# Analog_sensor_revA.net
KiCad netlist of a schematic drawn in EAGLE
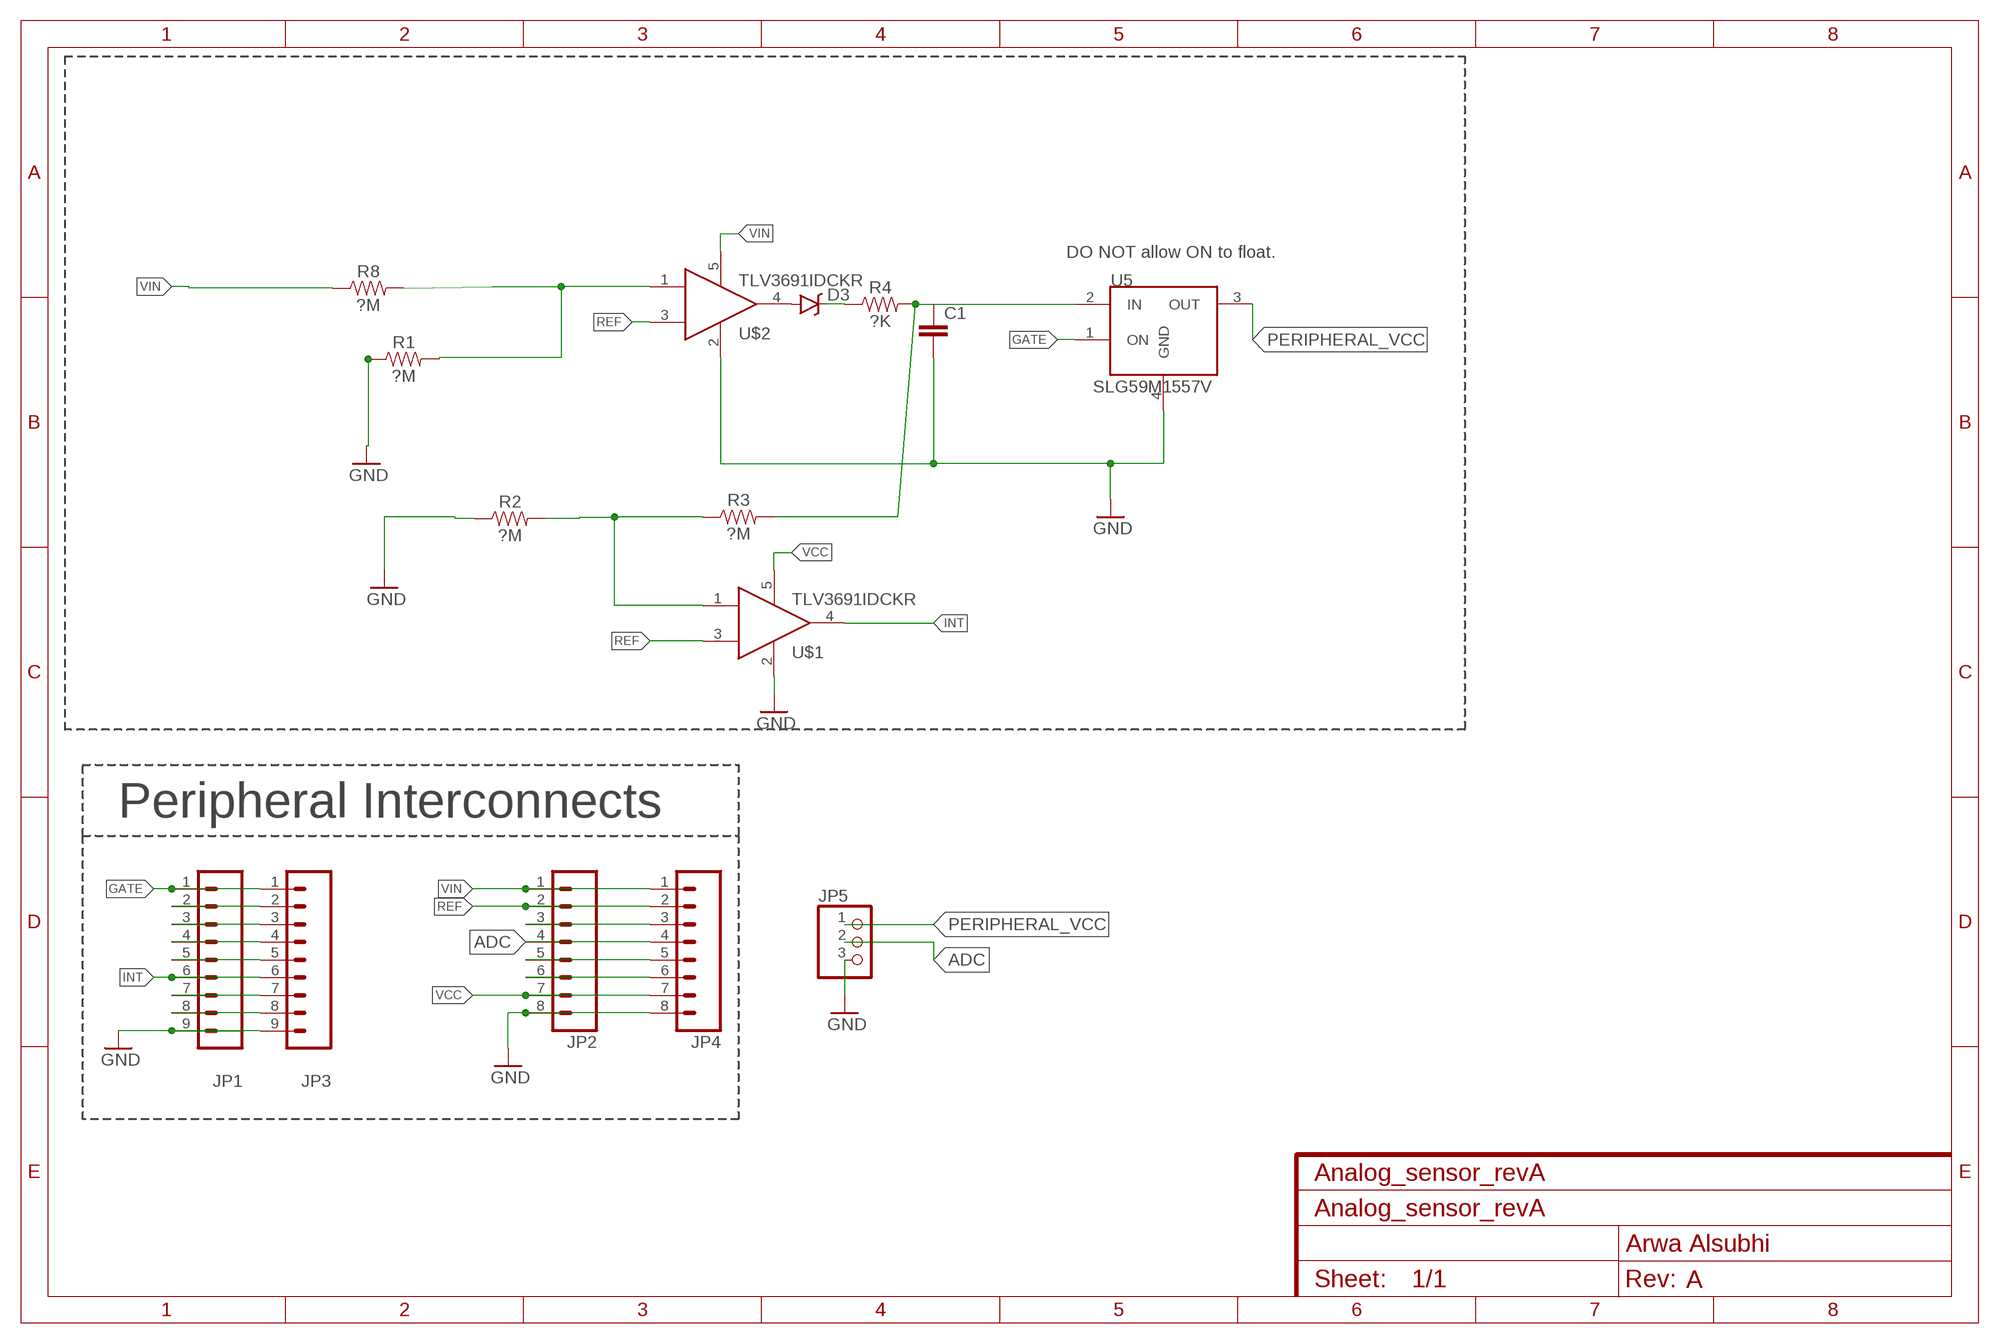
[diagram p0: schematic, sheet 1]

(export (version "E")
  (design (tool "Eeschema 10.0.6"))
  (components
    (comp (ref "C1")
      (value "CAP0603-CAP")
      (footprint "eagle-import:0603-CAP")
      (libsource (lib "eagle-import") (part "CAP0603-CAP"))
    )
    (comp (ref "D3")
      (value "RB751")
      (footprint "eagle-import:SOD-523")
      (fields (field (name "MPN") "BAS40-02V-V-G-08"))
      (libsource (lib "eagle-import") (part "DIODE-SCHOTTKY-RB751"))
    )
    (comp (ref "JP1")
      (value "M091.27MM")
      (footprint "eagle-import:1X09-1.27MM")
      (fields (field (name "MANUFACTURERPARTNUMBER") "GRPB091VWVN-RC ") (field (name "MPN") "GRPB091VWVN-RC"))
      (libsource (lib "eagle-import") (part "M091.27MM"))
    )
    (comp (ref "JP2")
      (value "M081.27MM")
      (footprint "eagle-import:1X08-1.27MM")
      (fields (field (name "MANUFACTURERPARTNUMBER") "GRPB081VWVN-RC "))
      (libsource (lib "eagle-import") (part "M081.27MM"))
    )
    (comp (ref "JP3")
      (value "M091.27MM")
      (footprint "eagle-import:1X09-1.27MM")
      (fields (field (name "MANUFACTURERPARTNUMBER") "GRPB091VWVN-RC ") (field (name "MPN") "GRPB091VWVN-RC"))
      (libsource (lib "eagle-import") (part "M091.27MM"))
    )
    (comp (ref "JP4")
      (value "M081.27MM")
      (footprint "eagle-import:1X08-1.27MM")
      (fields (field (name "MANUFACTURERPARTNUMBER") "GRPB081VWVN-RC "))
      (libsource (lib "eagle-import") (part "M081.27MM"))
    )
    (comp (ref "JP5")
      (value "PINHD-1X3")
      (footprint "eagle-import:1X03")
      (libsource (lib "eagle-import") (part "PINHD-1X3"))
    )
    (comp (ref "R1")
      (value "?M")
      (footprint "eagle-import:0805")
      (libsource (lib "eagle-import") (part "0.3OHM-0805-1/8W-1%"))
    )
    (comp (ref "R2")
      (value "?M")
      (footprint "eagle-import:0805")
      (libsource (lib "eagle-import") (part "0.3OHM-0805-1/8W-1%"))
    )
    (comp (ref "R3")
      (value "?M")
      (footprint "eagle-import:0805")
      (libsource (lib "eagle-import") (part "0.3OHM-0805-1/8W-1%"))
    )
    (comp (ref "R4")
      (value "?K")
      (footprint "eagle-import:0805")
      (libsource (lib "eagle-import") (part "0.3OHM-0805-1/8W-1%"))
    )
    (comp (ref "R8")
      (value "?M")
      (footprint "eagle-import:0805")
      (libsource (lib "eagle-import") (part "0.3OHM-0805-1/8W-1%"))
    )
    (comp (ref "U$1")
      (value "TLV3691IDCKR")
      (footprint "eagle-import:SOT353")
      (libsource (lib "eagle-import") (part "TLV3691IDCKR"))
    )
    (comp (ref "U$2")
      (value "TLV3691IDCKR")
      (footprint "eagle-import:SOT353")
      (libsource (lib "eagle-import") (part "TLV3691IDCKR"))
    )
    (comp (ref "U5")
      (value "SLG59M1557V")
      (footprint "eagle-import:4STDFN")
      (fields (field (name "MPN") "SLG59M1557V "))
      (libsource (lib "eagle-import") (part "SLG59M1557V"))
    )
  )
  (nets
    (net (code "1") (name "ADC") (class "Default")
      (node (ref "JP2") (pin "4") (pinfunction "4_4") (pintype "passive"))
      (node (ref "JP4") (pin "4") (pinfunction "4_4") (pintype "passive"))
      (node (ref "JP5") (pin "2") (pinfunction "2_2") (pintype "passive"))
    )
    (net (code "2") (name "GATE") (class "Default")
      (node (ref "JP1") (pin "1") (pinfunction "1_1") (pintype "passive"))
      (node (ref "JP3") (pin "1") (pinfunction "1_1") (pintype "passive"))
      (node (ref "U5") (pin "1") (pinfunction "ON_1") (pintype "bidirectional"))
    )
    (net (code "3") (name "GND") (class "Default")
      (node (ref "C1") (pin "2") (pinfunction "2_2") (pintype "passive"))
      (node (ref "JP1") (pin "9") (pinfunction "9_9") (pintype "passive"))
      (node (ref "JP2") (pin "8") (pinfunction "8_8") (pintype "passive"))
      (node (ref "JP3") (pin "9") (pinfunction "9_9") (pintype "passive"))
      (node (ref "JP4") (pin "8") (pinfunction "8_8") (pintype "passive"))
      (node (ref "JP5") (pin "3") (pinfunction "3_3") (pintype "passive"))
      (node (ref "R1") (pin "1") (pinfunction "1_1") (pintype "passive"))
      (node (ref "R2") (pin "1") (pinfunction "1_1") (pintype "passive"))
      (node (ref "U$1") (pin "2") (pinfunction "2_2") (pintype "bidirectional"))
      (node (ref "U$2") (pin "2") (pinfunction "2_2") (pintype "bidirectional"))
      (node (ref "U5") (pin "4") (pinfunction "GND_4") (pintype "bidirectional"))
    )
    (net (code "4") (name "INT") (class "Default")
      (node (ref "JP1") (pin "6") (pinfunction "6_6") (pintype "passive"))
      (node (ref "JP3") (pin "6") (pinfunction "6_6") (pintype "passive"))
      (node (ref "U$1") (pin "4") (pinfunction "4_4") (pintype "bidirectional"))
    )
    (net (code "5") (name "Net-(D3-PadA)") (class "Default")
      (node (ref "D3") (pin "A") (pinfunction "A_A") (pintype "passive"))
      (node (ref "U$2") (pin "4") (pinfunction "4_4") (pintype "bidirectional"))
    )
    (net (code "6") (name "Net-(D3-PadC)") (class "Default")
      (node (ref "D3") (pin "C") (pinfunction "C_C") (pintype "passive"))
      (node (ref "R4") (pin "1") (pinfunction "1_1") (pintype "passive"))
    )
    (net (code "7") (name "Net-(JP1-Pad2)") (class "Default")
      (node (ref "JP1") (pin "2") (pinfunction "2_2") (pintype "passive"))
      (node (ref "JP3") (pin "2") (pinfunction "2_2") (pintype "passive"))
    )
    (net (code "8") (name "Net-(JP1-Pad3)") (class "Default")
      (node (ref "JP1") (pin "3") (pinfunction "3_3") (pintype "passive"))
      (node (ref "JP3") (pin "3") (pinfunction "3_3") (pintype "passive"))
    )
    (net (code "9") (name "Net-(JP1-Pad4)") (class "Default")
      (node (ref "JP1") (pin "4") (pinfunction "4_4") (pintype "passive"))
      (node (ref "JP3") (pin "4") (pinfunction "4_4") (pintype "passive"))
    )
    (net (code "10") (name "Net-(JP1-Pad5)") (class "Default")
      (node (ref "JP1") (pin "5") (pinfunction "5_5") (pintype "passive"))
      (node (ref "JP3") (pin "5") (pinfunction "5_5") (pintype "passive"))
    )
    (net (code "11") (name "Net-(JP1-Pad7)") (class "Default")
      (node (ref "JP1") (pin "7") (pinfunction "7_7") (pintype "passive"))
      (node (ref "JP3") (pin "7") (pinfunction "7_7") (pintype "passive"))
    )
    (net (code "12") (name "Net-(JP1-Pad8)") (class "Default")
      (node (ref "JP1") (pin "8") (pinfunction "8_8") (pintype "passive"))
      (node (ref "JP3") (pin "8") (pinfunction "8_8") (pintype "passive"))
    )
    (net (code "13") (name "Net-(JP2-Pad3)") (class "Default")
      (node (ref "JP2") (pin "3") (pinfunction "3_3") (pintype "passive"))
      (node (ref "JP4") (pin "3") (pinfunction "3_3") (pintype "passive"))
    )
    (net (code "14") (name "Net-(JP2-Pad5)") (class "Default")
      (node (ref "JP2") (pin "5") (pinfunction "5_5") (pintype "passive"))
      (node (ref "JP4") (pin "5") (pinfunction "5_5") (pintype "passive"))
    )
    (net (code "15") (name "Net-(JP2-Pad6)") (class "Default")
      (node (ref "JP2") (pin "6") (pinfunction "6_6") (pintype "passive"))
      (node (ref "JP4") (pin "6") (pinfunction "6_6") (pintype "passive"))
    )
    (net (code "16") (name "Net-(R1-Pad2)") (class "Default")
      (node (ref "R1") (pin "2") (pinfunction "2_2") (pintype "passive"))
      (node (ref "R8") (pin "2") (pinfunction "2_2") (pintype "passive"))
      (node (ref "U$2") (pin "1") (pinfunction "1_1") (pintype "bidirectional"))
    )
    (net (code "17") (name "Net-(R2-Pad2)") (class "Default")
      (node (ref "R2") (pin "2") (pinfunction "2_2") (pintype "passive"))
      (node (ref "R3") (pin "1") (pinfunction "1_1") (pintype "passive"))
      (node (ref "U$1") (pin "1") (pinfunction "1_1") (pintype "bidirectional"))
    )
    (net (code "18") (name "Net-(U5-IN)") (class "Default")
      (node (ref "C1") (pin "1") (pinfunction "1_1") (pintype "passive"))
      (node (ref "R3") (pin "2") (pinfunction "2_2") (pintype "passive"))
      (node (ref "R4") (pin "2") (pinfunction "2_2") (pintype "passive"))
      (node (ref "U5") (pin "2") (pinfunction "IN_2") (pintype "bidirectional"))
    )
    (net (code "19") (name "PERIPHERAL_VCC") (class "Default")
      (node (ref "JP5") (pin "1") (pinfunction "1_1") (pintype "passive"))
      (node (ref "U5") (pin "3") (pinfunction "OUT_3") (pintype "bidirectional"))
    )
    (net (code "20") (name "REF") (class "Default")
      (node (ref "JP2") (pin "2") (pinfunction "2_2") (pintype "passive"))
      (node (ref "JP4") (pin "2") (pinfunction "2_2") (pintype "passive"))
      (node (ref "U$1") (pin "3") (pinfunction "3_3") (pintype "bidirectional"))
      (node (ref "U$2") (pin "3") (pinfunction "3_3") (pintype "bidirectional"))
    )
    (net (code "21") (name "VCC") (class "Default")
      (node (ref "JP2") (pin "7") (pinfunction "7_7") (pintype "passive"))
      (node (ref "JP4") (pin "7") (pinfunction "7_7") (pintype "passive"))
      (node (ref "U$1") (pin "5") (pinfunction "5_5") (pintype "bidirectional"))
    )
    (net (code "22") (name "VIN") (class "Default")
      (node (ref "JP2") (pin "1") (pinfunction "1_1") (pintype "passive"))
      (node (ref "JP4") (pin "1") (pinfunction "1_1") (pintype "passive"))
      (node (ref "R8") (pin "1") (pinfunction "1_1") (pintype "passive"))
      (node (ref "U$2") (pin "5") (pinfunction "5_5") (pintype "bidirectional"))
    )
  )
)
